# PWR_TLV71325.net
KiCad netlist of a schematic drawn in Altium Designer
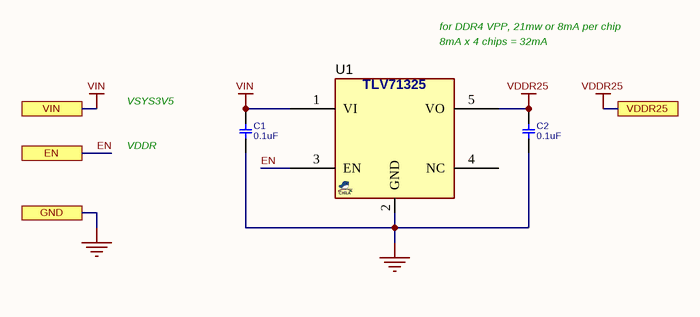
[diagram p0: PWR_TLV71325.SchDoc]

(export (version "E")
  (design (tool "Eeschema 10.0.6"))
  (components
    (comp (ref "C1")
      (value "0.1uF")
      (footprint "C0402")
      (description "CAP, MLCC")
      (fields (field (name "MANF_P#") "GRM155R61E104") (field (name "MANF") "Murata"))
      (libsource (lib "passive_smd") (part "CAP_SMD_MLCC"))
    )
    (comp (ref "C2")
      (value "0.1uF")
      (footprint "C0402")
      (description "CAP, MLCC")
      (fields (field (name "MANF_P#") "GRM155R61E104") (field (name "MANF") "Murata"))
      (libsource (lib "passive_smd") (part "CAP_SMD_MLCC"))
    )
    (comp (ref "U1")
      (value "TLV71325")
      (footprint "SOT23_5")
      (description "REG, Linear, LDO0.23V, 0.15A, 1.4~-5.5VIN, SOT23-5")
      (fields (field (name "MANF") "Texas Instruments") (field (name "MANF_P#") "TLV71325PDBV"))
      (libsource (lib "pwr_reg_linear_LDO_highPSRR") (part "VREG_TLV71325_SOT23"))
    )
  )
  (nets
    (net (code "1") (name "/EN") (class "Default")
      (node (ref "U1") (pin "3") (pinfunction "EN_3") (pintype "passive"))
    )
    (net (code "2") (name "GND") (class "Default")
      (node (ref "C1") (pin "1") (pinfunction "1_1") (pintype "passive"))
      (node (ref "C2") (pin "1") (pinfunction "1_1") (pintype "passive"))
      (node (ref "U1") (pin "2") (pinfunction "GND_2") (pintype "passive"))
    )
    (net (code "3") (name "VDDR25") (class "Default")
      (node (ref "C2") (pin "2") (pinfunction "2_2") (pintype "passive"))
      (node (ref "U1") (pin "5") (pinfunction "VO_5") (pintype "passive"))
    )
    (net (code "4") (name "VIN") (class "Default")
      (node (ref "C1") (pin "2") (pinfunction "2_2") (pintype "passive"))
      (node (ref "U1") (pin "1") (pinfunction "VI_1") (pintype "passive"))
    )
    (net (code "5") (name "unconnected-(U1-NC-Pad4)") (class "Default")
      (node (ref "U1") (pin "4") (pinfunction "NC_4") (pintype "passive"))
    )
  )
)
